# CT_v00.net
KiCad netlist of a schematic drawn in Altium Designer
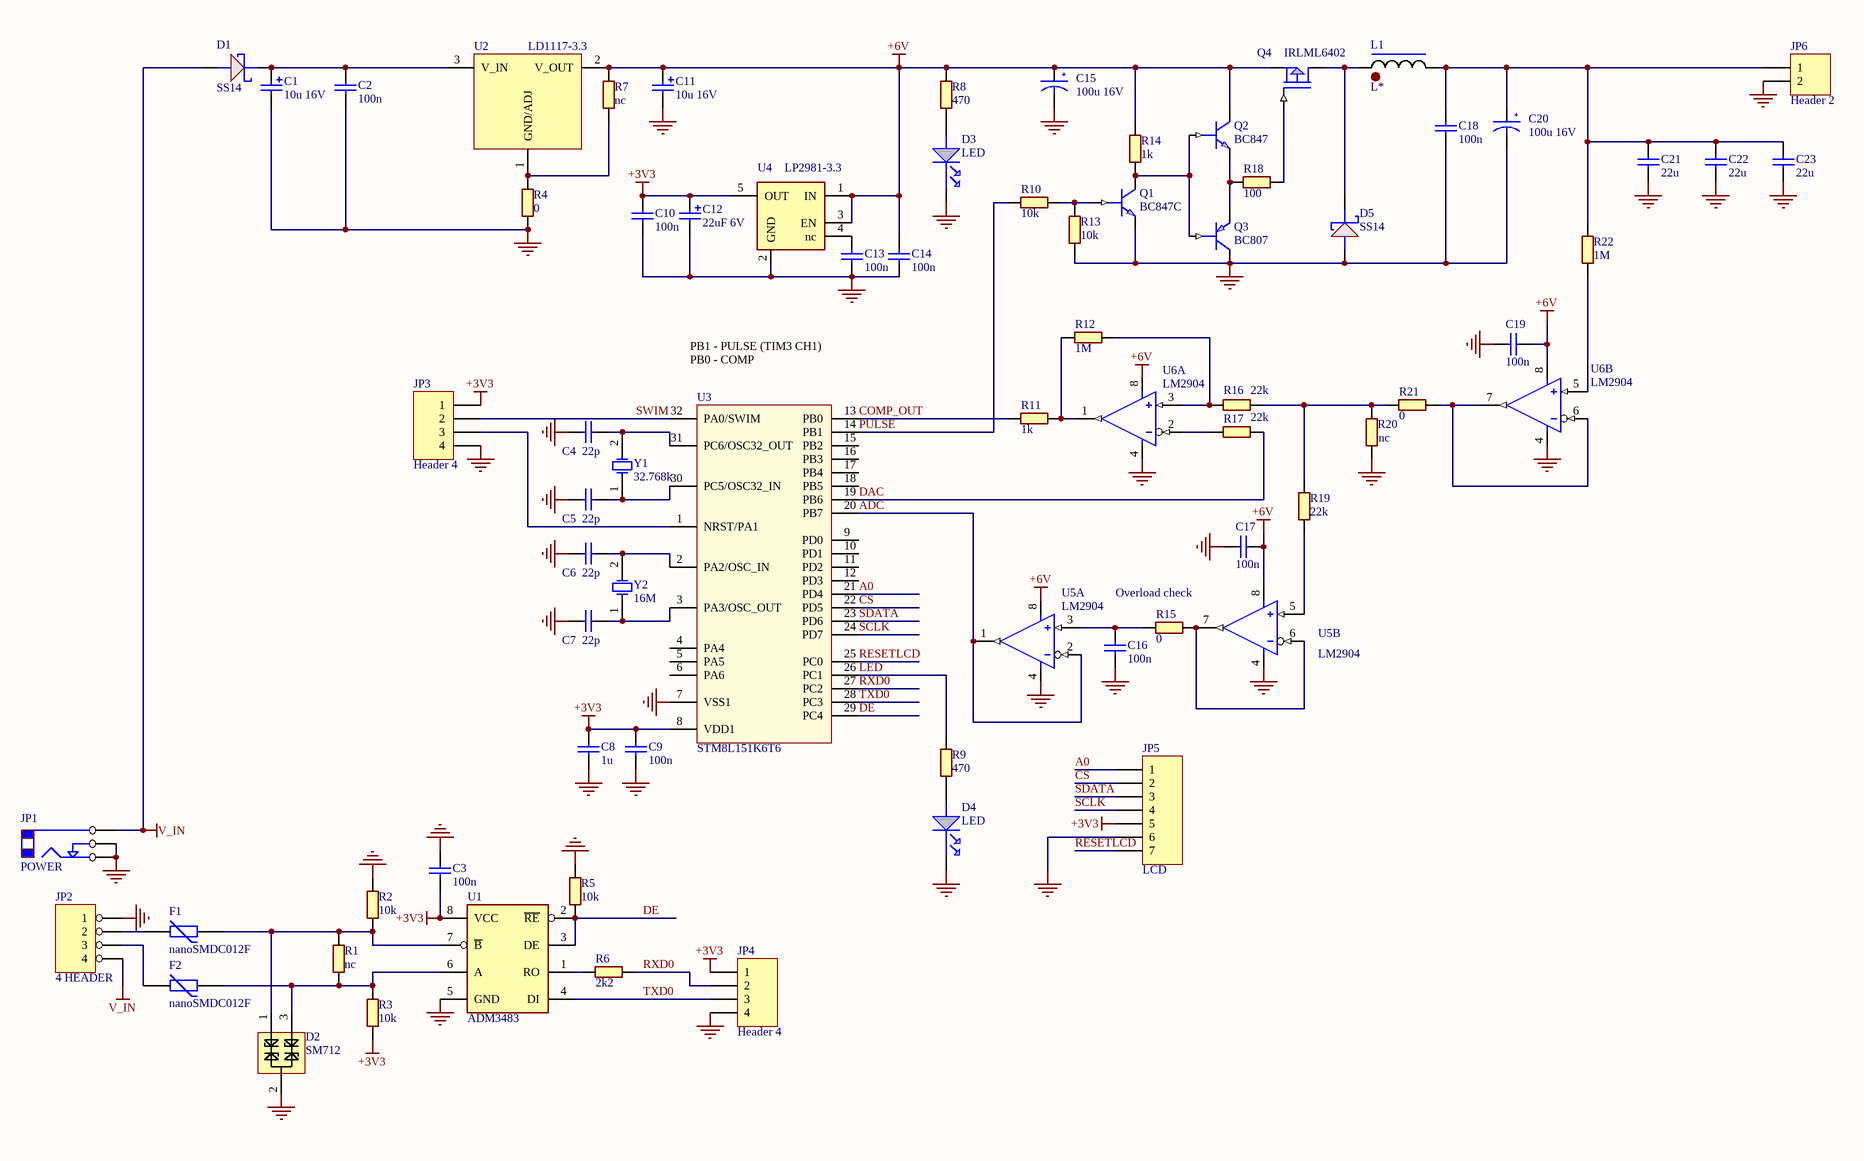
[diagram p0: CT_v00.SchDoc]

(export (version "E")
  (design (tool "Eeschema 10.0.6"))
  (components
    (comp (ref "C1") (value "10u 16V") (footprint "CAPMP3217X18N") (libsource (lib "Discrete") (part "CAPP")))
    (comp (ref "C2") (value "100n") (footprint "CAPC1608X08N") (libsource (lib "Discrete") (part "CAPN")))
    (comp (ref "C3") (value "100n") (footprint "CAPC1608X08N") (libsource (lib "Discrete") (part "CAPN")))
    (comp (ref "C4") (value "22p") (footprint "CAPC1608X08N") (libsource (lib "Discrete") (part "CAPN")))
    (comp (ref "C5") (value "22p") (footprint "CAPC1608X08N") (libsource (lib "Discrete") (part "CAPN")))
    (comp (ref "C6") (value "22p") (footprint "CAPC1608X08N") (libsource (lib "Discrete") (part "CAPN")))
    (comp (ref "C7") (value "22p") (footprint "CAPC1608X08N") (libsource (lib "Discrete") (part "CAPN")))
    (comp (ref "C8") (value "1u") (footprint "CAPC1608X08N") (libsource (lib "Discrete") (part "CAPN")))
    (comp (ref "C9") (value "100n") (footprint "CAPC1608X08N") (libsource (lib "Discrete") (part "CAPN")))
    (comp (ref "C10") (value "100n") (footprint "CAPC1608X08N") (libsource (lib "Discrete") (part "CAPN")))
    (comp (ref "C11")
      (value "10u 16V")
      (footprint "CAPMP3217X18N")
      (libsource (lib "Discrete") (part "CAPP"))
    )
    (comp (ref "C12")
      (value "22uF 6V")
      (footprint "CAPMP3217X18N")
      (libsource (lib "Discrete") (part "CAPP"))
    )
    (comp (ref "C13") (value "100n") (footprint "CAPC1608X08N") (libsource (lib "Discrete") (part "CAPN")))
    (comp (ref "C14") (value "100n") (footprint "CAPC1608X08N") (libsource (lib "Discrete") (part "CAPN")))
    (comp (ref "C15")
      (value "100u 16V")
      (footprint "CAPPRD200W50D600H1250")
      (libsource (lib "Discrete") (part "C-EL-DIP"))
    )
    (comp (ref "C16") (value "100n") (footprint "CAPC1608X08N") (libsource (lib "Discrete") (part "CAPN")))
    (comp (ref "C17") (value "100n") (footprint "CAPC1608X08N") (libsource (lib "Discrete") (part "CAPN")))
    (comp (ref "C18") (value "100n") (footprint "CAPC1608X08N") (libsource (lib "Discrete") (part "CAPN")))
    (comp (ref "C19") (value "100n") (footprint "CAPC1608X08N") (libsource (lib "Discrete") (part "CAPN")))
    (comp (ref "C20")
      (value "100u 16V")
      (footprint "CAPPRD200W50D600H1250")
      (libsource (lib "Discrete") (part "C-EL-DIP"))
    )
    (comp (ref "C21") (value "22u") (footprint "CAPC3216X14N") (libsource (lib "Discrete") (part "CAPN")))
    (comp (ref "C22") (value "22u") (footprint "CAPC3216X14N") (libsource (lib "Discrete") (part "CAPN")))
    (comp (ref "C23") (value "22u") (footprint "CAPC3216X14N") (libsource (lib "Discrete") (part "CAPN")))
    (comp (ref "D1")
      (value "SS14")
      (footprint "DIOM521X260X241L114X145N")
      (libsource (lib "Discrete") (part "DIODE SCHOTTKY"))
    )
    (comp (ref "D2") (value "SM712") (footprint "SOT-23") (libsource (lib "ul2016") (part "SM712")))
    (comp (ref "D3") (value "LED") (footprint "LEDC200X125X80L40N") (libsource (lib "Discrete") (part "LED")))
    (comp (ref "D4") (value "LED") (footprint "LEDC200X125X80L40N") (libsource (lib "Discrete") (part "LED")))
    (comp (ref "D5")
      (value "SS14")
      (footprint "DIOM521X260X241L114X145N")
      (libsource (lib "Discrete") (part "DIODE SCHOTTKY"))
    )
    (comp (ref "F1")
      (value "nanoSMDC012F")
      (footprint "RESC3216X07N")
      (libsource (lib "ul2016") (part "VARISTOR"))
    )
    (comp (ref "F2")
      (value "nanoSMDC012F")
      (footprint "RESC3216X07N")
      (libsource (lib "ul2016") (part "VARISTOR"))
    )
    (comp (ref "JP1")
      (value "POWER")
      (footprint "DC-140-003")
      (libsource (lib "Connectors$switces") (part "POWER"))
    )
    (comp (ref "JP2")
      (value "4 HEADER")
      (footprint "TERMINAL4")
      (description "4 Pin Header")
      (libsource (lib "Connectors$switces") (part "4 HEADER"))
    )
    (comp (ref "JP3")
      (value "Header 4")
      (footprint "HDRV4W70P254_4X1_889X254H754")
      (description "Header, 4-Pin")
      (fields (field (name "PUBLISHER") "Altium Limited"))
      (libsource (lib "Miscellaneous Connectors") (part "Header 4"))
    )
    (comp (ref "JP4")
      (value "Header 4")
      (footprint "HDRV4W70P254_4X1_889X254H754")
      (description "Header, 4-Pin")
      (fields (field (name "PUBLISHER") "Altium Limited"))
      (libsource (lib "") (part "Header 4_1"))
    )
    (comp (ref "JP5")
      (value "LCD")
      (footprint "HDRV7W70P254_7X1_1651X254H754")
      (description "Header, 7-Pin")
      (fields (field (name "PUBLISHER") "Altium Limited"))
      (libsource (lib "Miscellaneous Connectors") (part "Header 7"))
    )
    (comp (ref "JP6")
      (value "Header 2")
      (footprint "TERMINAL2")
      (description "Header, 2-Pin")
      (fields (field (name "PUBLISHER") "Altium Limited"))
      (libsource (lib "Miscellaneous Connectors") (part "Header 2"))
    )
    (comp (ref "L1") (value "L*") (footprint "SND-0705") (libsource (lib "Discrete") (part "L*")))
    (comp (ref "Q1")
      (value "BC847C")
      (footprint "SOT95P245X110-3N")
      (libsource (lib "Discrete") (part "NPN"))
    )
    (comp (ref "Q2") (value "BC847") (footprint "SOT95P245X110-3N") (libsource (lib "Discrete") (part "NPN")))
    (comp (ref "Q3") (value "BC807") (footprint "SOT95P245X110-3N") (libsource (lib "Discrete") (part "PNP")))
    (comp (ref "Q4") (value "IRLML6402") (footprint "SOT-23") (libsource (lib "Discrete") (part "MOSF-P")))
    (comp (ref "R1") (value "nc") (footprint "RESC1608X06N") (libsource (lib "") (part "RES_1")))
    (comp (ref "R2") (value "10k") (footprint "RESC1608X06N") (libsource (lib "") (part "RES_2")))
    (comp (ref "R3") (value "10k") (footprint "RESC1608X06N") (libsource (lib "") (part "RES_1")))
    (comp (ref "R4") (value "0") (footprint "RESC1608X06N") (libsource (lib "") (part "RES_2")))
    (comp (ref "R5") (value "10k") (footprint "RESC1608X06N") (libsource (lib "") (part "RES_1")))
    (comp (ref "R6") (value "2k2") (footprint "RESC1608X06N") (libsource (lib "Discrete") (part "RES")))
    (comp (ref "R7") (value "nc") (footprint "RESC1608X06N") (libsource (lib "") (part "RES_2")))
    (comp (ref "R8") (value "470") (footprint "RESC1608X06N") (libsource (lib "") (part "RES_1")))
    (comp (ref "R9") (value "470") (footprint "RESC1608X06N") (libsource (lib "") (part "RES_1")))
    (comp (ref "R10") (value "10k") (footprint "RESC1608X06N") (libsource (lib "Discrete") (part "RES")))
    (comp (ref "R11") (value "1k") (footprint "RESC1608X06N") (libsource (lib "Discrete") (part "RES")))
    (comp (ref "R12") (value "1M") (footprint "RESC1608X06N") (libsource (lib "Discrete") (part "RES")))
    (comp (ref "R13") (value "10k") (footprint "RESC1608X06N") (libsource (lib "") (part "RES_1")))
    (comp (ref "R14") (value "1k") (footprint "RESC1608X06N") (libsource (lib "") (part "RES_2")))
    (comp (ref "R15") (value "0") (footprint "RESC1608X06N") (libsource (lib "Discrete") (part "RES")))
    (comp (ref "R16") (value "22k") (footprint "RESC1608X06N") (libsource (lib "Discrete") (part "RES")))
    (comp (ref "R17") (value "22k") (footprint "RESC1608X06N") (libsource (lib "Discrete") (part "RES")))
    (comp (ref "R18") (value "100") (footprint "RESC1608X06N") (libsource (lib "Discrete") (part "RES")))
    (comp (ref "R19") (value "22k") (footprint "RESC1608X06N") (libsource (lib "") (part "RES_1")))
    (comp (ref "R20") (value "nc") (footprint "RESC1608X06N") (libsource (lib "") (part "RES_1")))
    (comp (ref "R21") (value "0") (footprint "RESC1608X06N") (libsource (lib "Discrete") (part "RES")))
    (comp (ref "R22") (value "1M") (footprint "RESC1608X06N") (libsource (lib "") (part "RES_2")))
    (comp (ref "U1")
      (value "ADM3483")
      (footprint "SOIC127P600X175-8N")
      (libsource (lib "ICs") (part "SN65HVD12DG4"))
    )
    (comp (ref "U2")
      (value "LD1117-3.3")
      (footprint "SOT230P700X180-4N")
      (libsource (lib "RFM_PS_V01") (part "LM1117_3.3"))
    )
    (comp (ref "U3")
      (value "STM8L151K6T6")
      (footprint "TQFP80P900X900X160-32N")
      (libsource (lib "CT") (part "STM8L151K6T6"))
    )
    (comp (ref "U4")
      (value "LP2981-3.3")
      (footprint "SOT95P245X110-5N")
      (libsource (lib "ICs") (part "LP2981-3.3"))
    )
    (comp (ref "U5")
      (value "LM2904")
      (footprint "SOIC127P600X175-8N")
      (description "2 Operation amplifier")
      (libsource (lib "ICs") (part "LM2904"))
    )
    (comp (ref "U6")
      (value "LM2904")
      (footprint "SOIC127P600X175-8N")
      (description "2 Operation amplifier")
      (libsource (lib "ICs") (part "LM2904"))
    )
    (comp (ref "Y1")
      (value "32.768k")
      (footprint "KX26")
      (description "Crystal Oscillator")
      (fields (field (name "PUBLISHER") "Altium Limited"))
      (libsource (lib "Miscellaneous Devices") (part "XTAL"))
    )
    (comp (ref "Y2")
      (value "16M")
      (footprint "XTAL_HC49P488W43L1117T475H350")
      (description "Crystal Oscillator")
      (fields (field (name "PUBLISHER") "Altium Limited"))
      (libsource (lib "Miscellaneous Devices") (part "XTAL"))
    )
  )
  (nets
    (net (code "1") (name "+3V3") (class "Default")
      (node (ref "C10") (pin "1") (pinfunction "1_1") (pintype "passive"))
      (node (ref "C12") (pin "2") (pinfunction "2_2") (pintype "passive"))
      (node (ref "C3") (pin "2") (pinfunction "2_2") (pintype "passive"))
      (node (ref "C8") (pin "1") (pinfunction "1_1") (pintype "passive"))
      (node (ref "C9") (pin "1") (pinfunction "1_1") (pintype "passive"))
      (node (ref "JP3") (pin "1") (pinfunction "1_1") (pintype "passive"))
      (node (ref "JP4") (pin "1") (pinfunction "1_1") (pintype "passive"))
      (node (ref "JP5") (pin "5") (pinfunction "5_5") (pintype "passive"))
      (node (ref "R3") (pin "2") (pinfunction "2_2") (pintype "passive"))
      (node (ref "U1") (pin "8") (pinfunction "VCC_8") (pintype "passive"))
      (node (ref "U3") (pin "8") (pinfunction "VDD1_8") (pintype "passive"))
      (node (ref "U4") (pin "5") (pinfunction "OUT_5") (pintype "passive"))
    )
    (net (code "2") (name "+6V") (class "Default")
      (node (ref "C11") (pin "2") (pinfunction "2_2") (pintype "passive"))
      (node (ref "C14") (pin "1") (pinfunction "1_1") (pintype "passive"))
      (node (ref "C15") (pin "2") (pinfunction "+_2") (pintype "passive"))
      (node (ref "C17") (pin "2") (pinfunction "2_2") (pintype "passive"))
      (node (ref "C19") (pin "2") (pinfunction "2_2") (pintype "passive"))
      (node (ref "Q2") (pin "2") (pinfunction "COLLECTOR_2") (pintype "passive"))
      (node (ref "Q4") (pin "3") (pinfunction "SOURCE_3") (pintype "passive"))
      (node (ref "R14") (pin "2") (pinfunction "2_2") (pintype "passive"))
      (node (ref "R7") (pin "2") (pinfunction "2_2") (pintype "passive"))
      (node (ref "R8") (pin "1") (pinfunction "1_1") (pintype "passive"))
      (node (ref "U2") (pin "2") (pinfunction "V_OUT_2") (pintype "passive"))
      (node (ref "U4") (pin "1") (pinfunction "IN_1") (pintype "passive"))
      (node (ref "U4") (pin "3") (pinfunction "EN_3") (pintype "passive"))
      (node (ref "U5") (pin "8") (pinfunction "V+_8") (pintype "passive"))
      (node (ref "U6") (pin "8") (pinfunction "V+_8") (pintype "power_in"))
    )
    (net (code "3") (name "/A0") (class "Default")
      (node (ref "JP5") (pin "1") (pinfunction "1_1") (pintype "passive"))
      (node (ref "U3") (pin "21") (pinfunction "PD4_21") (pintype "passive"))
    )
    (net (code "4") (name "/ADC") (class "Default")
      (node (ref "U3") (pin "20") (pinfunction "PB7_20") (pintype "passive"))
      (node (ref "U5") (pin "1") (pinfunction "OUT_1") (pintype "output"))
      (node (ref "U5") (pin "2") (pinfunction "-IN_2") (pintype "input"))
    )
    (net (code "5") (name "/COMP_OUT") (class "Default")
      (node (ref "R11") (pin "2") (pinfunction "2_2") (pintype "passive"))
      (node (ref "U3") (pin "13") (pinfunction "PB0_13") (pintype "passive"))
    )
    (net (code "6") (name "/CS") (class "Default")
      (node (ref "JP5") (pin "2") (pinfunction "2_2") (pintype "passive"))
      (node (ref "U3") (pin "22") (pinfunction "PD5_22") (pintype "passive"))
    )
    (net (code "7") (name "/DAC") (class "Default")
      (node (ref "R17") (pin "1") (pinfunction "1_1") (pintype "passive"))
      (node (ref "U3") (pin "19") (pinfunction "PB6_19") (pintype "passive"))
    )
    (net (code "8") (name "/DE") (class "Default")
      (node (ref "R5") (pin "2") (pinfunction "2_2") (pintype "passive"))
      (node (ref "U1") (pin "2") (pinfunction "~{RE}_2") (pintype "passive"))
      (node (ref "U1") (pin "3") (pinfunction "DE_3") (pintype "passive"))
      (node (ref "U3") (pin "29") (pinfunction "PC4_29") (pintype "passive"))
    )
    (net (code "9") (name "/LED") (class "Default")
      (node (ref "R9") (pin "1") (pinfunction "1_1") (pintype "passive"))
      (node (ref "U3") (pin "26") (pinfunction "PC1_26") (pintype "passive"))
    )
    (net (code "10") (name "/PULSE") (class "Default")
      (node (ref "R10") (pin "2") (pinfunction "2_2") (pintype "passive"))
      (node (ref "U3") (pin "14") (pinfunction "PB1_14") (pintype "passive"))
    )
    (net (code "11") (name "/RESETLCD") (class "Default")
      (node (ref "JP5") (pin "7") (pinfunction "7_7") (pintype "passive"))
      (node (ref "U3") (pin "25") (pinfunction "PC0_25") (pintype "passive"))
    )
    (net (code "12") (name "/RXD0") (class "Default")
      (node (ref "JP4") (pin "2") (pinfunction "2_2") (pintype "passive"))
      (node (ref "R6") (pin "1") (pinfunction "1_1") (pintype "passive"))
      (node (ref "U3") (pin "27") (pinfunction "PC2_27") (pintype "passive"))
    )
    (net (code "13") (name "/SCLK") (class "Default")
      (node (ref "JP5") (pin "4") (pinfunction "4_4") (pintype "passive"))
      (node (ref "U3") (pin "24") (pinfunction "PD7_24") (pintype "passive"))
    )
    (net (code "14") (name "/SDATA") (class "Default")
      (node (ref "JP5") (pin "3") (pinfunction "3_3") (pintype "passive"))
      (node (ref "U3") (pin "23") (pinfunction "PD6_23") (pintype "passive"))
    )
    (net (code "15") (name "/SWIM") (class "Default")
      (node (ref "JP3") (pin "2") (pinfunction "2_2") (pintype "passive"))
      (node (ref "U3") (pin "32") (pinfunction "PA0/SWIM_32") (pintype "passive"))
    )
    (net (code "16") (name "/TXD0") (class "Default")
      (node (ref "JP4") (pin "3") (pinfunction "3_3") (pintype "passive"))
      (node (ref "U1") (pin "4") (pinfunction "DI_4") (pintype "passive"))
      (node (ref "U3") (pin "28") (pinfunction "PC3_28") (pintype "passive"))
    )
    (net (code "17") (name "GND") (class "Default")
      (node (ref "C1") (pin "1") (pinfunction "1_1") (pintype "passive"))
      (node (ref "C10") (pin "2") (pinfunction "2_2") (pintype "passive"))
      (node (ref "C11") (pin "1") (pinfunction "1_1") (pintype "passive"))
      (node (ref "C12") (pin "1") (pinfunction "1_1") (pintype "passive"))
      (node (ref "C13") (pin "2") (pinfunction "2_2") (pintype "passive"))
      (node (ref "C14") (pin "2") (pinfunction "2_2") (pintype "passive"))
      (node (ref "C15") (pin "1") (pinfunction "-_1") (pintype "passive"))
      (node (ref "C16") (pin "2") (pinfunction "2_2") (pintype "passive"))
      (node (ref "C17") (pin "1") (pinfunction "1_1") (pintype "passive"))
      (node (ref "C18") (pin "2") (pinfunction "2_2") (pintype "passive"))
      (node (ref "C19") (pin "1") (pinfunction "1_1") (pintype "passive"))
      (node (ref "C2") (pin "2") (pinfunction "2_2") (pintype "passive"))
      (node (ref "C20") (pin "1") (pinfunction "-_1") (pintype "passive"))
      (node (ref "C21") (pin "2") (pinfunction "2_2") (pintype "passive"))
      (node (ref "C22") (pin "2") (pinfunction "2_2") (pintype "passive"))
      (node (ref "C23") (pin "2") (pinfunction "2_2") (pintype "passive"))
      (node (ref "C3") (pin "1") (pinfunction "1_1") (pintype "passive"))
      (node (ref "C4") (pin "1") (pinfunction "1_1") (pintype "passive"))
      (node (ref "C5") (pin "1") (pinfunction "1_1") (pintype "passive"))
      (node (ref "C6") (pin "1") (pinfunction "1_1") (pintype "passive"))
      (node (ref "C7") (pin "1") (pinfunction "1_1") (pintype "passive"))
      (node (ref "C8") (pin "2") (pinfunction "2_2") (pintype "passive"))
      (node (ref "C9") (pin "2") (pinfunction "2_2") (pintype "passive"))
      (node (ref "D2") (pin "2") (pinfunction "2_2") (pintype "passive"))
      (node (ref "D3") (pin "K") (pinfunction "CATHODE_K") (pintype "passive"))
      (node (ref "D4") (pin "K") (pinfunction "CATHODE_K") (pintype "passive"))
      (node (ref "D5") (pin "A") (pinfunction "A_A") (pintype "passive"))
      (node (ref "JP1") (pin "2") (pinfunction "C_2") (pintype "passive"))
      (node (ref "JP1") (pin "3") (pinfunction "B_3") (pintype "passive"))
      (node (ref "JP2") (pin "1") (pinfunction "1_1") (pintype "passive"))
      (node (ref "JP3") (pin "4") (pinfunction "4_4") (pintype "passive"))
      (node (ref "JP4") (pin "4") (pinfunction "4_4") (pintype "passive"))
      (node (ref "JP5") (pin "6") (pinfunction "6_6") (pintype "passive"))
      (node (ref "JP6") (pin "2") (pinfunction "2_2") (pintype "passive"))
      (node (ref "Q1") (pin "3") (pinfunction "EMITTER_3") (pintype "passive"))
      (node (ref "Q3") (pin "2") (pinfunction "COLLECTOR_2") (pintype "passive"))
      (node (ref "R13") (pin "2") (pinfunction "2_2") (pintype "passive"))
      (node (ref "R2") (pin "2") (pinfunction "2_2") (pintype "passive"))
      (node (ref "R20") (pin "2") (pinfunction "2_2") (pintype "passive"))
      (node (ref "R4") (pin "1") (pinfunction "1_1") (pintype "passive"))
      (node (ref "R5") (pin "1") (pinfunction "1_1") (pintype "passive"))
      (node (ref "U1") (pin "5") (pinfunction "GND_5") (pintype "passive"))
      (node (ref "U3") (pin "7") (pinfunction "VSS1_7") (pintype "passive"))
      (node (ref "U4") (pin "2") (pinfunction "GND_2") (pintype "passive"))
      (node (ref "U5") (pin "4") (pinfunction "V-_4") (pintype "passive"))
      (node (ref "U6") (pin "4") (pinfunction "V-_4") (pintype "passive"))
    )
    (net (code "18") (name "Net-(C20-+)") (class "Default")
      (node (ref "C18") (pin "1") (pinfunction "1_1") (pintype "passive"))
      (node (ref "C20") (pin "2") (pinfunction "+_2") (pintype "passive"))
      (node (ref "C21") (pin "1") (pinfunction "1_1") (pintype "passive"))
      (node (ref "C22") (pin "1") (pinfunction "1_1") (pintype "passive"))
      (node (ref "C23") (pin "1") (pinfunction "1_1") (pintype "passive"))
      (node (ref "JP6") (pin "1") (pinfunction "1_1") (pintype "passive"))
      (node (ref "L1") (pin "2") (pinfunction "2_2") (pintype "passive"))
      (node (ref "R22") (pin "2") (pinfunction "2_2") (pintype "passive"))
    )
    (net (code "19") (name "Net-(D3-ANODE)") (class "Default")
      (node (ref "D3") (pin "A") (pinfunction "ANODE_A") (pintype "passive"))
      (node (ref "R8") (pin "2") (pinfunction "2_2") (pintype "passive"))
    )
    (net (code "20") (name "Net-(D4-ANODE)") (class "Default")
      (node (ref "D4") (pin "A") (pinfunction "ANODE_A") (pintype "passive"))
      (node (ref "R9") (pin "2") (pinfunction "2_2") (pintype "passive"))
    )
    (net (code "21") (name "Net-(F1-Pad1)") (class "Default")
      (node (ref "F1") (pin "1") (pinfunction "1_1") (pintype "passive"))
      (node (ref "JP2") (pin "2") (pinfunction "2_2") (pintype "passive"))
    )
    (net (code "22") (name "Net-(F2-Pad1)") (class "Default")
      (node (ref "F2") (pin "1") (pinfunction "1_1") (pintype "passive"))
      (node (ref "JP2") (pin "3") (pinfunction "3_3") (pintype "passive"))
    )
    (net (code "23") (name "Net-(Q1-BASE)") (class "Default")
      (node (ref "Q1") (pin "1") (pinfunction "BASE_1") (pintype "input"))
      (node (ref "R10") (pin "1") (pinfunction "1_1") (pintype "passive"))
      (node (ref "R13") (pin "1") (pinfunction "1_1") (pintype "passive"))
    )
    (net (code "24") (name "Net-(Q1-COLLECTOR)") (class "Default")
      (node (ref "Q1") (pin "2") (pinfunction "COLLECTOR_2") (pintype "passive"))
      (node (ref "Q2") (pin "1") (pinfunction "BASE_1") (pintype "input"))
      (node (ref "Q3") (pin "1") (pinfunction "BASE_1") (pintype "input"))
      (node (ref "R14") (pin "1") (pinfunction "1_1") (pintype "passive"))
    )
    (net (code "25") (name "Net-(Q2-EMITTER)") (class "Default")
      (node (ref "Q2") (pin "3") (pinfunction "EMITTER_3") (pintype "passive"))
      (node (ref "Q3") (pin "3") (pinfunction "EMITTER_3") (pintype "passive"))
      (node (ref "R18") (pin "2") (pinfunction "2_2") (pintype "passive"))
    )
    (net (code "26") (name "Net-(Q4-DRAIN)") (class "Default")
      (node (ref "D5") (pin "K") (pinfunction "K_K") (pintype "passive"))
      (node (ref "L1") (pin "1") (pinfunction "1_1") (pintype "passive"))
      (node (ref "Q4") (pin "2") (pinfunction "DRAIN_2") (pintype "passive"))
    )
    (net (code "27") (name "Net-(Q4-GATE)") (class "Default")
      (node (ref "Q4") (pin "1") (pinfunction "GATE_1") (pintype "input"))
      (node (ref "R18") (pin "1") (pinfunction "1_1") (pintype "passive"))
    )
    (net (code "28") (name "Net-(R16-Pad1)") (class "Default")
      (node (ref "R16") (pin "1") (pinfunction "1_1") (pintype "passive"))
      (node (ref "R19") (pin "1") (pinfunction "1_1") (pintype "passive"))
      (node (ref "R20") (pin "1") (pinfunction "1_1") (pintype "passive"))
      (node (ref "R21") (pin "2") (pinfunction "2_2") (pintype "passive"))
    )
    (net (code "29") (name "Net-(U1-A)") (class "Default")
      (node (ref "D2") (pin "3") (pinfunction "3_3") (pintype "passive"))
      (node (ref "F2") (pin "2") (pinfunction "2_2") (pintype "passive"))
      (node (ref "R1") (pin "2") (pinfunction "2_2") (pintype "passive"))
      (node (ref "R3") (pin "1") (pinfunction "1_1") (pintype "passive"))
      (node (ref "U1") (pin "6") (pinfunction "A_6") (pintype "passive"))
    )
    (net (code "30") (name "Net-(U1-RO)") (class "Default")
      (node (ref "R6") (pin "2") (pinfunction "2_2") (pintype "passive"))
      (node (ref "U1") (pin "1") (pinfunction "RO_1") (pintype "passive"))
    )
    (net (code "31") (name "Net-(U1-~{B})") (class "Default")
      (node (ref "D2") (pin "1") (pinfunction "1_1") (pintype "passive"))
      (node (ref "F1") (pin "2") (pinfunction "2_2") (pintype "passive"))
      (node (ref "R1") (pin "1") (pinfunction "1_1") (pintype "passive"))
      (node (ref "R2") (pin "1") (pinfunction "1_1") (pintype "passive"))
      (node (ref "U1") (pin "7") (pinfunction "~{B}_7") (pintype "passive"))
    )
    (net (code "32") (name "Net-(U2-GND{slash}ADJ)") (class "Default")
      (node (ref "R4") (pin "2") (pinfunction "2_2") (pintype "passive"))
      (node (ref "R7") (pin "1") (pinfunction "1_1") (pintype "passive"))
      (node (ref "U2") (pin "1") (pinfunction "GND/ADJ_1") (pintype "passive"))
    )
    (net (code "33") (name "Net-(U2-V_IN)") (class "Default")
      (node (ref "C1") (pin "2") (pinfunction "2_2") (pintype "passive"))
      (node (ref "C2") (pin "1") (pinfunction "1_1") (pintype "passive"))
      (node (ref "D1") (pin "K") (pinfunction "K_K") (pintype "passive"))
      (node (ref "U2") (pin "3") (pinfunction "V_IN_3") (pintype "passive"))
    )
    (net (code "34") (name "Net-(U3-NRST{slash}PA1)") (class "Default")
      (node (ref "JP3") (pin "3") (pinfunction "3_3") (pintype "passive"))
      (node (ref "U3") (pin "1") (pinfunction "NRST/PA1_1") (pintype "passive"))
    )
    (net (code "35") (name "Net-(U3-PA2{slash}OSC_IN)") (class "Default")
      (node (ref "C6") (pin "2") (pinfunction "2_2") (pintype "passive"))
      (node (ref "U3") (pin "2") (pinfunction "PA2/OSC_IN_2") (pintype "passive"))
      (node (ref "Y2") (pin "2") (pinfunction "OSC2_2") (pintype "passive"))
    )
    (net (code "36") (name "Net-(U3-PA3{slash}OSC_OUT)") (class "Default")
      (node (ref "C7") (pin "2") (pinfunction "2_2") (pintype "passive"))
      (node (ref "U3") (pin "3") (pinfunction "PA3/OSC_OUT_3") (pintype "passive"))
      (node (ref "Y2") (pin "1") (pinfunction "OSC1_1") (pintype "passive"))
    )
    (net (code "37") (name "Net-(U3-PC5{slash}OSC32_IN)") (class "Default")
      (node (ref "C5") (pin "2") (pinfunction "2_2") (pintype "passive"))
      (node (ref "U3") (pin "30") (pinfunction "PC5/OSC32_IN_30") (pintype "passive"))
      (node (ref "Y1") (pin "1") (pinfunction "OSC1_1") (pintype "passive"))
    )
    (net (code "38") (name "Net-(U3-PC6{slash}OSC32_OUT)") (class "Default")
      (node (ref "C4") (pin "2") (pinfunction "2_2") (pintype "passive"))
      (node (ref "U3") (pin "31") (pinfunction "PC6/OSC32_OUT_31") (pintype "passive"))
      (node (ref "Y1") (pin "2") (pinfunction "OSC2_2") (pintype "passive"))
    )
    (net (code "39") (name "Net-(U4-nc)") (class "Default")
      (node (ref "C13") (pin "1") (pinfunction "1_1") (pintype "passive"))
      (node (ref "U4") (pin "4") (pinfunction "nc_4") (pintype "passive"))
    )
    (net (code "40") (name "Net-(U5A-+IN)") (class "Default")
      (node (ref "C16") (pin "1") (pinfunction "1_1") (pintype "passive"))
      (node (ref "R15") (pin "2") (pinfunction "2_2") (pintype "passive"))
      (node (ref "U5") (pin "3") (pinfunction "+IN_3") (pintype "input"))
    )
    (net (code "41") (name "Net-(U5B-+IN)") (class "Default")
      (node (ref "R19") (pin "2") (pinfunction "2_2") (pintype "passive"))
      (node (ref "U5") (pin "5") (pinfunction "+IN_5") (pintype "input"))
    )
    (net (code "42") (name "Net-(U5B--IN)") (class "Default")
      (node (ref "R15") (pin "1") (pinfunction "1_1") (pintype "passive"))
      (node (ref "U5") (pin "6") (pinfunction "-IN_6") (pintype "input"))
      (node (ref "U5") (pin "7") (pinfunction "OUT_7") (pintype "output"))
    )
    (net (code "43") (name "Net-(U6A-+IN)") (class "Default")
      (node (ref "R12") (pin "1") (pinfunction "1_1") (pintype "passive"))
      (node (ref "R16") (pin "2") (pinfunction "2_2") (pintype "passive"))
      (node (ref "U6") (pin "3") (pinfunction "+IN_3") (pintype "input"))
    )
    (net (code "44") (name "Net-(U6A--IN)") (class "Default")
      (node (ref "R17") (pin "2") (pinfunction "2_2") (pintype "passive"))
      (node (ref "U6") (pin "2") (pinfunction "-IN_2") (pintype "input"))
    )
    (net (code "45") (name "Net-(U6A-OUT)") (class "Default")
      (node (ref "R11") (pin "1") (pinfunction "1_1") (pintype "passive"))
      (node (ref "R12") (pin "2") (pinfunction "2_2") (pintype "passive"))
      (node (ref "U6") (pin "1") (pinfunction "OUT_1") (pintype "output"))
    )
    (net (code "46") (name "Net-(U6B-+IN)") (class "Default")
      (node (ref "R22") (pin "1") (pinfunction "1_1") (pintype "passive"))
      (node (ref "U6") (pin "5") (pinfunction "+IN_5") (pintype "input"))
    )
    (net (code "47") (name "Net-(U6B--IN)") (class "Default")
      (node (ref "R21") (pin "1") (pinfunction "1_1") (pintype "passive"))
      (node (ref "U6") (pin "6") (pinfunction "-IN_6") (pintype "input"))
      (node (ref "U6") (pin "7") (pinfunction "OUT_7") (pintype "output"))
    )
    (net (code "48") (name "V_IN") (class "Default")
      (node (ref "D1") (pin "A") (pinfunction "A_A") (pintype "passive"))
      (node (ref "JP1") (pin "1") (pinfunction "A_1") (pintype "passive"))
      (node (ref "JP2") (pin "4") (pinfunction "4_4") (pintype "passive"))
    )
    (net (code "49") (name "unconnected-(U3-PA4-Pad4)") (class "Default")
      (node (ref "U3") (pin "4") (pinfunction "PA4_4") (pintype "passive"))
    )
    (net (code "50") (name "unconnected-(U3-PA5-Pad5)") (class "Default")
      (node (ref "U3") (pin "5") (pinfunction "PA5_5") (pintype "passive"))
    )
    (net (code "51") (name "unconnected-(U3-PA6-Pad6)") (class "Default")
      (node (ref "U3") (pin "6") (pinfunction "PA6_6") (pintype "passive"))
    )
    (net (code "52") (name "unconnected-(U3-PB2-Pad15)") (class "Default")
      (node (ref "U3") (pin "15") (pinfunction "PB2_15") (pintype "passive"))
    )
    (net (code "53") (name "unconnected-(U3-PB3-Pad16)") (class "Default")
      (node (ref "U3") (pin "16") (pinfunction "PB3_16") (pintype "passive"))
    )
    (net (code "54") (name "unconnected-(U3-PB4-Pad17)") (class "Default")
      (node (ref "U3") (pin "17") (pinfunction "PB4_17") (pintype "passive"))
    )
    (net (code "55") (name "unconnected-(U3-PB5-Pad18)") (class "Default")
      (node (ref "U3") (pin "18") (pinfunction "PB5_18") (pintype "passive"))
    )
    (net (code "56") (name "unconnected-(U3-PD0-Pad9)") (class "Default")
      (node (ref "U3") (pin "9") (pinfunction "PD0_9") (pintype "passive"))
    )
    (net (code "57") (name "unconnected-(U3-PD1-Pad10)") (class "Default")
      (node (ref "U3") (pin "10") (pinfunction "PD1_10") (pintype "passive"))
    )
    (net (code "58") (name "unconnected-(U3-PD2-Pad11)") (class "Default")
      (node (ref "U3") (pin "11") (pinfunction "PD2_11") (pintype "passive"))
    )
    (net (code "59") (name "unconnected-(U3-PD3-Pad12)") (class "Default")
      (node (ref "U3") (pin "12") (pinfunction "PD3_12") (pintype "passive"))
    )
  )
)
